# eib-64-large.net
KiCad netlist of a schematic drawn in EAGLE
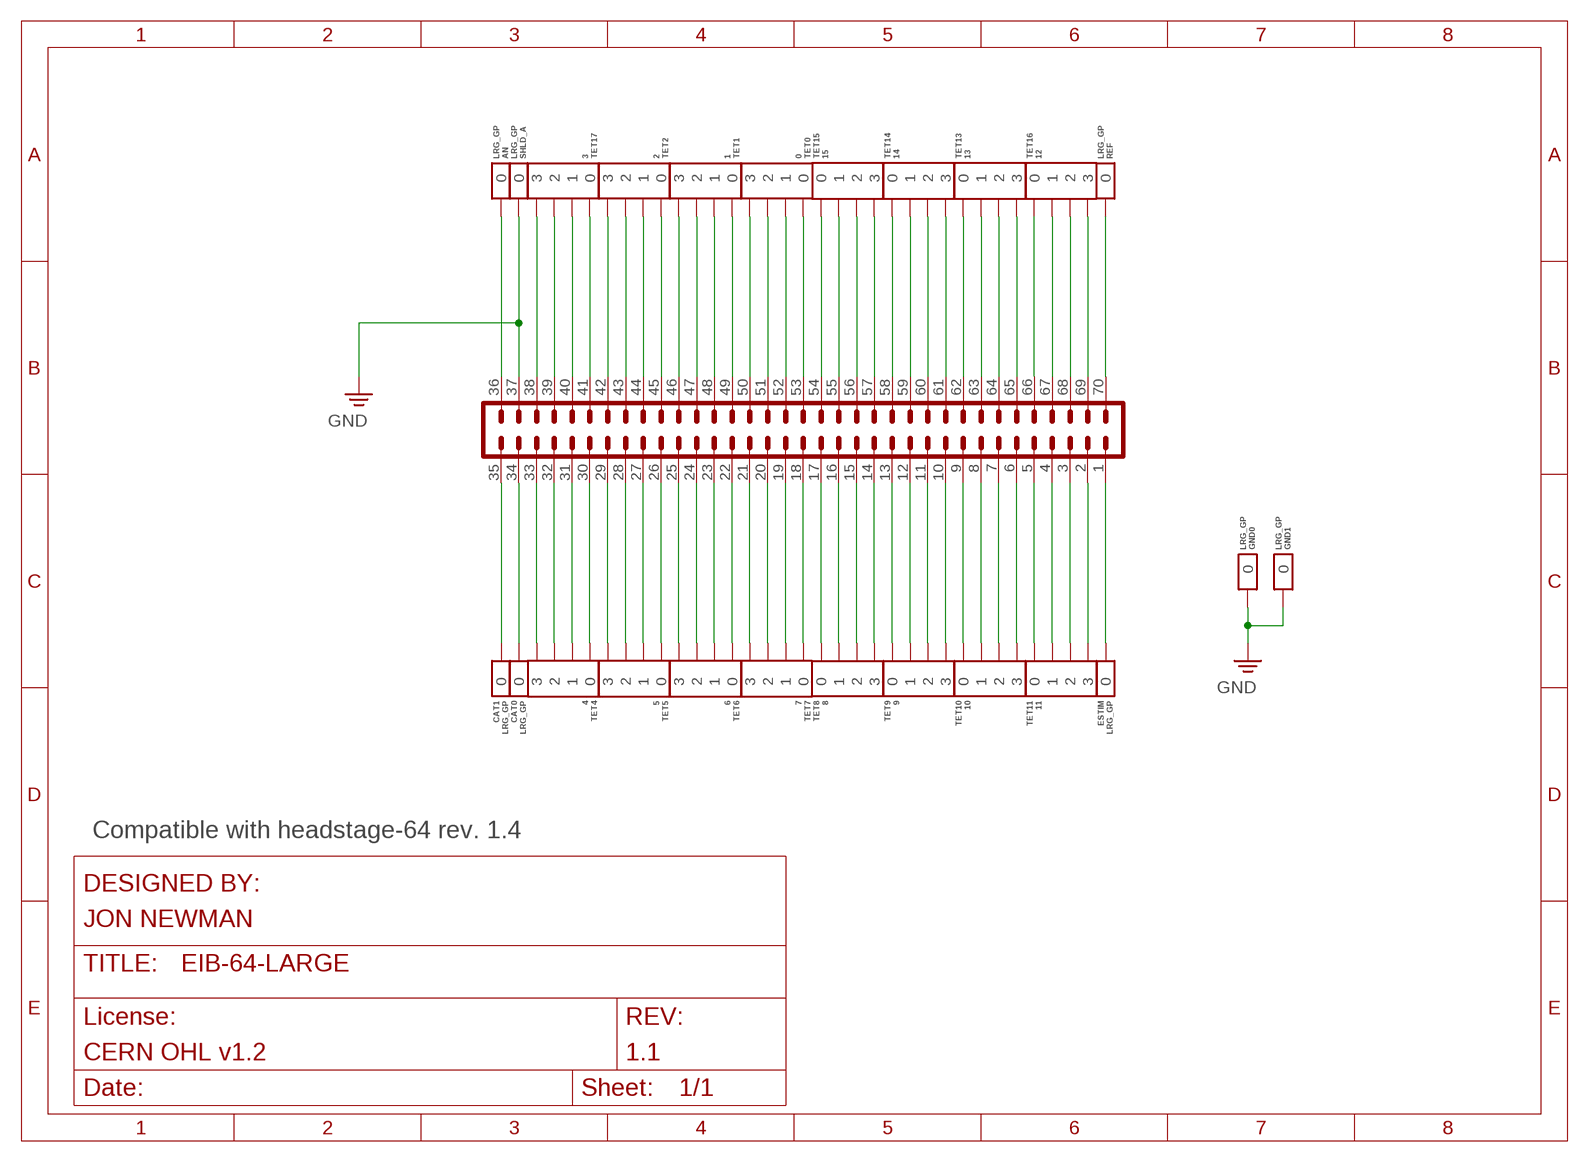
[diagram p0: schematic, sheet 1]

(export (version "E")
  (design (tool "Eeschema 10.0.6"))
  (components
    (comp (ref "AN")
      (value "LRG_GP")
      (footprint "eagle-import:GOLDPIN_0.5ID_0.7OD")
      (libsource (lib "eagle-import") (part "GOLDPIN_0.5ID_0.7OD"))
    )
    (comp (ref "CAT0")
      (value "LRG_GP")
      (footprint "eagle-import:GOLDPIN_0.5ID_0.7OD")
      (libsource (lib "eagle-import") (part "GOLDPIN_0.5ID_0.7OD"))
    )
    (comp (ref "CAT1")
      (value "LRG_GP")
      (footprint "eagle-import:GOLDPIN_0.5ID_0.7OD")
      (libsource (lib "eagle-import") (part "GOLDPIN_0.5ID_0.7OD"))
    )
    (comp (ref "ESTIM")
      (value "LRG_GP")
      (footprint "eagle-import:GOLDPIN_0.5ID_0.7OD")
      (libsource (lib "eagle-import") (part "GOLDPIN_0.5ID_0.7OD"))
    )
    (comp (ref "GND0")
      (value "LRG_GP")
      (footprint "eagle-import:GOLDPIN_0.5ID_0.7OD")
      (libsource (lib "eagle-import") (part "GOLDPIN_0.5ID_0.7OD"))
    )
    (comp (ref "GND1")
      (value "LRG_GP")
      (footprint "eagle-import:GOLDPIN_0.5ID_0.7OD")
      (libsource (lib "eagle-import") (part "GOLDPIN_0.5ID_0.7OD"))
    )
    (comp (ref "J1")
      (value "DF40-REC")
      (footprint "eagle-import:DDF40-70REC-LRG")
      (libsource (lib "eagle-import") (part "PINHD-2X35_DF40REF-LRG"))
    )
    (comp (ref "REF")
      (value "LRG_GP")
      (footprint "eagle-import:GOLDPIN_0.5ID_0.7OD")
      (libsource (lib "eagle-import") (part "GOLDPIN_0.5ID_0.7OD"))
    )
    (comp (ref "SHLD_A")
      (value "LRG_GP")
      (footprint "eagle-import:GOLDPIN_0.5ID_0.7OD")
      (libsource (lib "eagle-import") (part "GOLDPIN_0.5ID_0.7OD"))
    )
    (comp (ref "TET0")
      (value "0")
      (footprint "eagle-import:TETRODE_128_0.5ID_0.7OD")
      (libsource (lib "eagle-import") (part "TETRODE_128_0.5ID_0.7OD"))
    )
    (comp (ref "TET1")
      (value "1")
      (footprint "eagle-import:TETRODE_128_0.5ID_0.7OD")
      (libsource (lib "eagle-import") (part "TETRODE_128_0.5ID_0.7OD"))
    )
    (comp (ref "TET2")
      (value "2")
      (footprint "eagle-import:TETRODE_128_0.5ID_0.7OD")
      (libsource (lib "eagle-import") (part "TETRODE_128_0.5ID_0.7OD"))
    )
    (comp (ref "TET4")
      (value "4")
      (footprint "eagle-import:TETRODE_128_0.5ID_0.7OD")
      (libsource (lib "eagle-import") (part "TETRODE_128_0.5ID_0.7OD"))
    )
    (comp (ref "TET5")
      (value "5")
      (footprint "eagle-import:TETRODE_128_0.5ID_0.7OD")
      (libsource (lib "eagle-import") (part "TETRODE_128_0.5ID_0.7OD"))
    )
    (comp (ref "TET6")
      (value "6")
      (footprint "eagle-import:TETRODE_128_0.5ID_0.7OD")
      (libsource (lib "eagle-import") (part "TETRODE_128_0.5ID_0.7OD"))
    )
    (comp (ref "TET7")
      (value "7")
      (footprint "eagle-import:TETRODE_128_0.5ID_0.7OD")
      (libsource (lib "eagle-import") (part "TETRODE_128_0.5ID_0.7OD"))
    )
    (comp (ref "TET8")
      (value "8")
      (footprint "eagle-import:TETRODE_128_0.5ID_0.7OD")
      (libsource (lib "eagle-import") (part "TETRODE_128_0.5ID_0.7OD"))
    )
    (comp (ref "TET9")
      (value "9")
      (footprint "eagle-import:TETRODE_128_0.5ID_0.7OD")
      (libsource (lib "eagle-import") (part "TETRODE_128_0.5ID_0.7OD"))
    )
    (comp (ref "TET10")
      (value "10")
      (footprint "eagle-import:TETRODE_128_0.5ID_0.7OD")
      (libsource (lib "eagle-import") (part "TETRODE_128_0.5ID_0.7OD"))
    )
    (comp (ref "TET11")
      (value "11")
      (footprint "eagle-import:TETRODE_128_0.5ID_0.7OD")
      (libsource (lib "eagle-import") (part "TETRODE_128_0.5ID_0.7OD"))
    )
    (comp (ref "TET13")
      (value "13")
      (footprint "eagle-import:TETRODE_128_0.5ID_0.7OD")
      (libsource (lib "eagle-import") (part "TETRODE_128_0.5ID_0.7OD"))
    )
    (comp (ref "TET14")
      (value "14")
      (footprint "eagle-import:TETRODE_128_0.5ID_0.7OD")
      (libsource (lib "eagle-import") (part "TETRODE_128_0.5ID_0.7OD"))
    )
    (comp (ref "TET15")
      (value "15")
      (footprint "eagle-import:TETRODE_128_0.5ID_0.7OD")
      (libsource (lib "eagle-import") (part "TETRODE_128_0.5ID_0.7OD"))
    )
    (comp (ref "TET16")
      (value "12")
      (footprint "eagle-import:TETRODE_128_0.5ID_0.7OD")
      (libsource (lib "eagle-import") (part "TETRODE_128_0.5ID_0.7OD"))
    )
    (comp (ref "TET17")
      (value "3")
      (footprint "eagle-import:TETRODE_128_0.5ID_0.7OD")
      (libsource (lib "eagle-import") (part "TETRODE_128_0.5ID_0.7OD"))
    )
  )
  (nets
    (net (code "1") (name "GND") (class "Default")
      (node (ref "GND0") (pin "P$1") (pinfunction "0_P$1") (pintype "bidirectional"))
      (node (ref "GND1") (pin "P$1") (pinfunction "0_P$1") (pintype "bidirectional"))
      (node (ref "J1") (pin "37") (pinfunction "37_37") (pintype "bidirectional"))
      (node (ref "SHLD_A") (pin "P$1") (pinfunction "0_P$1") (pintype "bidirectional"))
    )
    (net (code "2") (name "Net-(AN-0)") (class "Default")
      (node (ref "AN") (pin "P$1") (pinfunction "0_P$1") (pintype "bidirectional"))
      (node (ref "J1") (pin "36") (pinfunction "36_36") (pintype "bidirectional"))
    )
    (net (code "3") (name "Net-(CAT0-0)") (class "Default")
      (node (ref "CAT0") (pin "P$1") (pinfunction "0_P$1") (pintype "bidirectional"))
      (node (ref "J1") (pin "34") (pinfunction "34_34") (pintype "bidirectional"))
    )
    (net (code "4") (name "Net-(CAT1-0)") (class "Default")
      (node (ref "CAT1") (pin "P$1") (pinfunction "0_P$1") (pintype "bidirectional"))
      (node (ref "J1") (pin "35") (pinfunction "35_35") (pintype "bidirectional"))
    )
    (net (code "5") (name "Net-(ESTIM-0)") (class "Default")
      (node (ref "ESTIM") (pin "P$1") (pinfunction "0_P$1") (pintype "bidirectional"))
      (node (ref "J1") (pin "1") (pinfunction "1_1") (pintype "bidirectional"))
    )
    (net (code "6") (name "Net-(J1-Pad2)") (class "Default")
      (node (ref "J1") (pin "2") (pinfunction "2_2") (pintype "bidirectional"))
      (node (ref "TET11") (pin "3") (pinfunction "3_3") (pintype "bidirectional"))
    )
    (net (code "7") (name "Net-(J1-Pad3)") (class "Default")
      (node (ref "J1") (pin "3") (pinfunction "3_3") (pintype "bidirectional"))
      (node (ref "TET11") (pin "2") (pinfunction "2_2") (pintype "bidirectional"))
    )
    (net (code "8") (name "Net-(J1-Pad4)") (class "Default")
      (node (ref "J1") (pin "4") (pinfunction "4_4") (pintype "bidirectional"))
      (node (ref "TET11") (pin "1") (pinfunction "1_1") (pintype "bidirectional"))
    )
    (net (code "9") (name "Net-(J1-Pad5)") (class "Default")
      (node (ref "J1") (pin "5") (pinfunction "5_5") (pintype "bidirectional"))
      (node (ref "TET11") (pin "0") (pinfunction "0_0") (pintype "bidirectional"))
    )
    (net (code "10") (name "Net-(J1-Pad6)") (class "Default")
      (node (ref "J1") (pin "6") (pinfunction "6_6") (pintype "bidirectional"))
      (node (ref "TET10") (pin "3") (pinfunction "3_3") (pintype "bidirectional"))
    )
    (net (code "11") (name "Net-(J1-Pad7)") (class "Default")
      (node (ref "J1") (pin "7") (pinfunction "7_7") (pintype "bidirectional"))
      (node (ref "TET10") (pin "2") (pinfunction "2_2") (pintype "bidirectional"))
    )
    (net (code "12") (name "Net-(J1-Pad8)") (class "Default")
      (node (ref "J1") (pin "8") (pinfunction "8_8") (pintype "bidirectional"))
      (node (ref "TET10") (pin "1") (pinfunction "1_1") (pintype "bidirectional"))
    )
    (net (code "13") (name "Net-(J1-Pad9)") (class "Default")
      (node (ref "J1") (pin "9") (pinfunction "9_9") (pintype "bidirectional"))
      (node (ref "TET10") (pin "0") (pinfunction "0_0") (pintype "bidirectional"))
    )
    (net (code "14") (name "Net-(J1-Pad10)") (class "Default")
      (node (ref "J1") (pin "10") (pinfunction "10_10") (pintype "bidirectional"))
      (node (ref "TET9") (pin "3") (pinfunction "3_3") (pintype "bidirectional"))
    )
    (net (code "15") (name "Net-(J1-Pad11)") (class "Default")
      (node (ref "J1") (pin "11") (pinfunction "11_11") (pintype "bidirectional"))
      (node (ref "TET9") (pin "2") (pinfunction "2_2") (pintype "bidirectional"))
    )
    (net (code "16") (name "Net-(J1-Pad12)") (class "Default")
      (node (ref "J1") (pin "12") (pinfunction "12_12") (pintype "bidirectional"))
      (node (ref "TET9") (pin "1") (pinfunction "1_1") (pintype "bidirectional"))
    )
    (net (code "17") (name "Net-(J1-Pad13)") (class "Default")
      (node (ref "J1") (pin "13") (pinfunction "13_13") (pintype "bidirectional"))
      (node (ref "TET9") (pin "0") (pinfunction "0_0") (pintype "bidirectional"))
    )
    (net (code "18") (name "Net-(J1-Pad14)") (class "Default")
      (node (ref "J1") (pin "14") (pinfunction "14_14") (pintype "bidirectional"))
      (node (ref "TET8") (pin "3") (pinfunction "3_3") (pintype "bidirectional"))
    )
    (net (code "19") (name "Net-(J1-Pad15)") (class "Default")
      (node (ref "J1") (pin "15") (pinfunction "15_15") (pintype "bidirectional"))
      (node (ref "TET8") (pin "2") (pinfunction "2_2") (pintype "bidirectional"))
    )
    (net (code "20") (name "Net-(J1-Pad16)") (class "Default")
      (node (ref "J1") (pin "16") (pinfunction "16_16") (pintype "bidirectional"))
      (node (ref "TET8") (pin "1") (pinfunction "1_1") (pintype "bidirectional"))
    )
    (net (code "21") (name "Net-(J1-Pad17)") (class "Default")
      (node (ref "J1") (pin "17") (pinfunction "17_17") (pintype "bidirectional"))
      (node (ref "TET8") (pin "0") (pinfunction "0_0") (pintype "bidirectional"))
    )
    (net (code "22") (name "Net-(J1-Pad18)") (class "Default")
      (node (ref "J1") (pin "18") (pinfunction "18_18") (pintype "bidirectional"))
      (node (ref "TET7") (pin "0") (pinfunction "0_0") (pintype "bidirectional"))
    )
    (net (code "23") (name "Net-(J1-Pad19)") (class "Default")
      (node (ref "J1") (pin "19") (pinfunction "19_19") (pintype "bidirectional"))
      (node (ref "TET7") (pin "1") (pinfunction "1_1") (pintype "bidirectional"))
    )
    (net (code "24") (name "Net-(J1-Pad20)") (class "Default")
      (node (ref "J1") (pin "20") (pinfunction "20_20") (pintype "bidirectional"))
      (node (ref "TET7") (pin "2") (pinfunction "2_2") (pintype "bidirectional"))
    )
    (net (code "25") (name "Net-(J1-Pad21)") (class "Default")
      (node (ref "J1") (pin "21") (pinfunction "21_21") (pintype "bidirectional"))
      (node (ref "TET7") (pin "3") (pinfunction "3_3") (pintype "bidirectional"))
    )
    (net (code "26") (name "Net-(J1-Pad22)") (class "Default")
      (node (ref "J1") (pin "22") (pinfunction "22_22") (pintype "bidirectional"))
      (node (ref "TET6") (pin "0") (pinfunction "0_0") (pintype "bidirectional"))
    )
    (net (code "27") (name "Net-(J1-Pad23)") (class "Default")
      (node (ref "J1") (pin "23") (pinfunction "23_23") (pintype "bidirectional"))
      (node (ref "TET6") (pin "1") (pinfunction "1_1") (pintype "bidirectional"))
    )
    (net (code "28") (name "Net-(J1-Pad24)") (class "Default")
      (node (ref "J1") (pin "24") (pinfunction "24_24") (pintype "bidirectional"))
      (node (ref "TET6") (pin "2") (pinfunction "2_2") (pintype "bidirectional"))
    )
    (net (code "29") (name "Net-(J1-Pad25)") (class "Default")
      (node (ref "J1") (pin "25") (pinfunction "25_25") (pintype "bidirectional"))
      (node (ref "TET6") (pin "3") (pinfunction "3_3") (pintype "bidirectional"))
    )
    (net (code "30") (name "Net-(J1-Pad26)") (class "Default")
      (node (ref "J1") (pin "26") (pinfunction "26_26") (pintype "bidirectional"))
      (node (ref "TET5") (pin "0") (pinfunction "0_0") (pintype "bidirectional"))
    )
    (net (code "31") (name "Net-(J1-Pad27)") (class "Default")
      (node (ref "J1") (pin "27") (pinfunction "27_27") (pintype "bidirectional"))
      (node (ref "TET5") (pin "1") (pinfunction "1_1") (pintype "bidirectional"))
    )
    (net (code "32") (name "Net-(J1-Pad28)") (class "Default")
      (node (ref "J1") (pin "28") (pinfunction "28_28") (pintype "bidirectional"))
      (node (ref "TET5") (pin "2") (pinfunction "2_2") (pintype "bidirectional"))
    )
    (net (code "33") (name "Net-(J1-Pad29)") (class "Default")
      (node (ref "J1") (pin "29") (pinfunction "29_29") (pintype "bidirectional"))
      (node (ref "TET5") (pin "3") (pinfunction "3_3") (pintype "bidirectional"))
    )
    (net (code "34") (name "Net-(J1-Pad30)") (class "Default")
      (node (ref "J1") (pin "30") (pinfunction "30_30") (pintype "bidirectional"))
      (node (ref "TET4") (pin "0") (pinfunction "0_0") (pintype "bidirectional"))
    )
    (net (code "35") (name "Net-(J1-Pad31)") (class "Default")
      (node (ref "J1") (pin "31") (pinfunction "31_31") (pintype "bidirectional"))
      (node (ref "TET4") (pin "1") (pinfunction "1_1") (pintype "bidirectional"))
    )
    (net (code "36") (name "Net-(J1-Pad32)") (class "Default")
      (node (ref "J1") (pin "32") (pinfunction "32_32") (pintype "bidirectional"))
      (node (ref "TET4") (pin "2") (pinfunction "2_2") (pintype "bidirectional"))
    )
    (net (code "37") (name "Net-(J1-Pad33)") (class "Default")
      (node (ref "J1") (pin "33") (pinfunction "33_33") (pintype "bidirectional"))
      (node (ref "TET4") (pin "3") (pinfunction "3_3") (pintype "bidirectional"))
    )
    (net (code "38") (name "Net-(J1-Pad38)") (class "Default")
      (node (ref "J1") (pin "38") (pinfunction "38_38") (pintype "bidirectional"))
      (node (ref "TET17") (pin "3") (pinfunction "3_3") (pintype "bidirectional"))
    )
    (net (code "39") (name "Net-(J1-Pad39)") (class "Default")
      (node (ref "J1") (pin "39") (pinfunction "39_39") (pintype "bidirectional"))
      (node (ref "TET17") (pin "2") (pinfunction "2_2") (pintype "bidirectional"))
    )
    (net (code "40") (name "Net-(J1-Pad40)") (class "Default")
      (node (ref "J1") (pin "40") (pinfunction "40_40") (pintype "bidirectional"))
      (node (ref "TET17") (pin "1") (pinfunction "1_1") (pintype "bidirectional"))
    )
    (net (code "41") (name "Net-(J1-Pad41)") (class "Default")
      (node (ref "J1") (pin "41") (pinfunction "41_41") (pintype "bidirectional"))
      (node (ref "TET17") (pin "0") (pinfunction "0_0") (pintype "bidirectional"))
    )
    (net (code "42") (name "Net-(J1-Pad42)") (class "Default")
      (node (ref "J1") (pin "42") (pinfunction "42_42") (pintype "bidirectional"))
      (node (ref "TET2") (pin "3") (pinfunction "3_3") (pintype "bidirectional"))
    )
    (net (code "43") (name "Net-(J1-Pad43)") (class "Default")
      (node (ref "J1") (pin "43") (pinfunction "43_43") (pintype "bidirectional"))
      (node (ref "TET2") (pin "2") (pinfunction "2_2") (pintype "bidirectional"))
    )
    (net (code "44") (name "Net-(J1-Pad44)") (class "Default")
      (node (ref "J1") (pin "44") (pinfunction "44_44") (pintype "bidirectional"))
      (node (ref "TET2") (pin "1") (pinfunction "1_1") (pintype "bidirectional"))
    )
    (net (code "45") (name "Net-(J1-Pad45)") (class "Default")
      (node (ref "J1") (pin "45") (pinfunction "45_45") (pintype "bidirectional"))
      (node (ref "TET2") (pin "0") (pinfunction "0_0") (pintype "bidirectional"))
    )
    (net (code "46") (name "Net-(J1-Pad46)") (class "Default")
      (node (ref "J1") (pin "46") (pinfunction "46_46") (pintype "bidirectional"))
      (node (ref "TET1") (pin "3") (pinfunction "3_3") (pintype "bidirectional"))
    )
    (net (code "47") (name "Net-(J1-Pad47)") (class "Default")
      (node (ref "J1") (pin "47") (pinfunction "47_47") (pintype "bidirectional"))
      (node (ref "TET1") (pin "2") (pinfunction "2_2") (pintype "bidirectional"))
    )
    (net (code "48") (name "Net-(J1-Pad48)") (class "Default")
      (node (ref "J1") (pin "48") (pinfunction "48_48") (pintype "bidirectional"))
      (node (ref "TET1") (pin "1") (pinfunction "1_1") (pintype "bidirectional"))
    )
    (net (code "49") (name "Net-(J1-Pad49)") (class "Default")
      (node (ref "J1") (pin "49") (pinfunction "49_49") (pintype "bidirectional"))
      (node (ref "TET1") (pin "0") (pinfunction "0_0") (pintype "bidirectional"))
    )
    (net (code "50") (name "Net-(J1-Pad50)") (class "Default")
      (node (ref "J1") (pin "50") (pinfunction "50_50") (pintype "bidirectional"))
      (node (ref "TET0") (pin "3") (pinfunction "3_3") (pintype "bidirectional"))
    )
    (net (code "51") (name "Net-(J1-Pad51)") (class "Default")
      (node (ref "J1") (pin "51") (pinfunction "51_51") (pintype "bidirectional"))
      (node (ref "TET0") (pin "2") (pinfunction "2_2") (pintype "bidirectional"))
    )
    (net (code "52") (name "Net-(J1-Pad52)") (class "Default")
      (node (ref "J1") (pin "52") (pinfunction "52_52") (pintype "bidirectional"))
      (node (ref "TET0") (pin "1") (pinfunction "1_1") (pintype "bidirectional"))
    )
    (net (code "53") (name "Net-(J1-Pad53)") (class "Default")
      (node (ref "J1") (pin "53") (pinfunction "53_53") (pintype "bidirectional"))
      (node (ref "TET0") (pin "0") (pinfunction "0_0") (pintype "bidirectional"))
    )
    (net (code "54") (name "Net-(J1-Pad54)") (class "Default")
      (node (ref "J1") (pin "54") (pinfunction "54_54") (pintype "bidirectional"))
      (node (ref "TET15") (pin "0") (pinfunction "0_0") (pintype "bidirectional"))
    )
    (net (code "55") (name "Net-(J1-Pad55)") (class "Default")
      (node (ref "J1") (pin "55") (pinfunction "55_55") (pintype "bidirectional"))
      (node (ref "TET15") (pin "1") (pinfunction "1_1") (pintype "bidirectional"))
    )
    (net (code "56") (name "Net-(J1-Pad56)") (class "Default")
      (node (ref "J1") (pin "56") (pinfunction "56_56") (pintype "bidirectional"))
      (node (ref "TET15") (pin "2") (pinfunction "2_2") (pintype "bidirectional"))
    )
    (net (code "57") (name "Net-(J1-Pad57)") (class "Default")
      (node (ref "J1") (pin "57") (pinfunction "57_57") (pintype "bidirectional"))
      (node (ref "TET15") (pin "3") (pinfunction "3_3") (pintype "bidirectional"))
    )
    (net (code "58") (name "Net-(J1-Pad58)") (class "Default")
      (node (ref "J1") (pin "58") (pinfunction "58_58") (pintype "bidirectional"))
      (node (ref "TET14") (pin "0") (pinfunction "0_0") (pintype "bidirectional"))
    )
    (net (code "59") (name "Net-(J1-Pad59)") (class "Default")
      (node (ref "J1") (pin "59") (pinfunction "59_59") (pintype "bidirectional"))
      (node (ref "TET14") (pin "1") (pinfunction "1_1") (pintype "bidirectional"))
    )
    (net (code "60") (name "Net-(J1-Pad60)") (class "Default")
      (node (ref "J1") (pin "60") (pinfunction "60_60") (pintype "bidirectional"))
      (node (ref "TET14") (pin "2") (pinfunction "2_2") (pintype "bidirectional"))
    )
    (net (code "61") (name "Net-(J1-Pad61)") (class "Default")
      (node (ref "J1") (pin "61") (pinfunction "61_61") (pintype "bidirectional"))
      (node (ref "TET14") (pin "3") (pinfunction "3_3") (pintype "bidirectional"))
    )
    (net (code "62") (name "Net-(J1-Pad62)") (class "Default")
      (node (ref "J1") (pin "62") (pinfunction "62_62") (pintype "bidirectional"))
      (node (ref "TET13") (pin "0") (pinfunction "0_0") (pintype "bidirectional"))
    )
    (net (code "63") (name "Net-(J1-Pad63)") (class "Default")
      (node (ref "J1") (pin "63") (pinfunction "63_63") (pintype "bidirectional"))
      (node (ref "TET13") (pin "1") (pinfunction "1_1") (pintype "bidirectional"))
    )
    (net (code "64") (name "Net-(J1-Pad64)") (class "Default")
      (node (ref "J1") (pin "64") (pinfunction "64_64") (pintype "bidirectional"))
      (node (ref "TET13") (pin "2") (pinfunction "2_2") (pintype "bidirectional"))
    )
    (net (code "65") (name "Net-(J1-Pad65)") (class "Default")
      (node (ref "J1") (pin "65") (pinfunction "65_65") (pintype "bidirectional"))
      (node (ref "TET13") (pin "3") (pinfunction "3_3") (pintype "bidirectional"))
    )
    (net (code "66") (name "Net-(J1-Pad66)") (class "Default")
      (node (ref "J1") (pin "66") (pinfunction "66_66") (pintype "bidirectional"))
      (node (ref "TET16") (pin "0") (pinfunction "0_0") (pintype "bidirectional"))
    )
    (net (code "67") (name "Net-(J1-Pad67)") (class "Default")
      (node (ref "J1") (pin "67") (pinfunction "67_67") (pintype "bidirectional"))
      (node (ref "TET16") (pin "1") (pinfunction "1_1") (pintype "bidirectional"))
    )
    (net (code "68") (name "Net-(J1-Pad68)") (class "Default")
      (node (ref "J1") (pin "68") (pinfunction "68_68") (pintype "bidirectional"))
      (node (ref "TET16") (pin "2") (pinfunction "2_2") (pintype "bidirectional"))
    )
    (net (code "69") (name "Net-(J1-Pad69)") (class "Default")
      (node (ref "J1") (pin "69") (pinfunction "69_69") (pintype "bidirectional"))
      (node (ref "TET16") (pin "3") (pinfunction "3_3") (pintype "bidirectional"))
    )
    (net (code "70") (name "Net-(REF-0)") (class "Default")
      (node (ref "J1") (pin "70") (pinfunction "70_70") (pintype "bidirectional"))
      (node (ref "REF") (pin "P$1") (pinfunction "0_P$1") (pintype "bidirectional"))
    )
  )
)
